# Accelerometer.net
KiCad netlist of a schematic drawn in Altium Designer
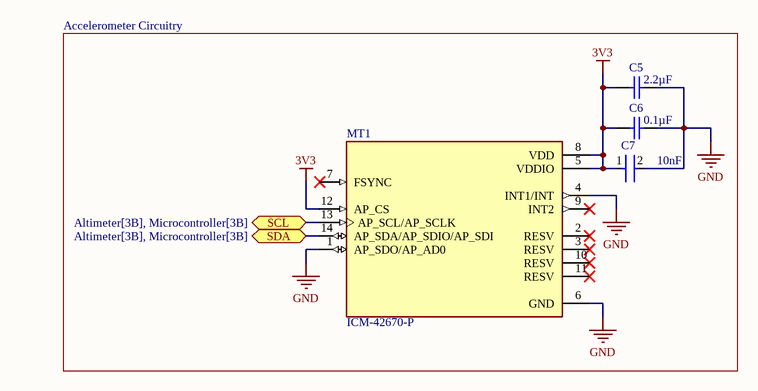
[diagram p0: Accelerometer.SchDoc]

(export (version "E")
  (design (tool "Eeschema 10.0.6"))
  (components
    (comp (ref "C5")
      (value "2.2µF")
      (footprint "CAPC3216X180X50LL20T25")
      (description "Chip Capacitor, 2.2 uF, +/- 10%, 50 V, -55 to 125 degC, 1206 (3216 Metric), RoHS, Tape and Reel")
      (fields (field (name "MANUFACTURER") "Kemet") (field (name "TOLERANCE") "10%"))
      (libsource (lib "Altium Content Vault") (part "CAP-NP-2"))
    )
    (comp (ref "C6")
      (value "0.1µF")
      (footprint "CAPC3216X100X50LL20T25")
      (description "Chip Capacitor, 100 nF, +/- 10%, 25 V, -55 to 125 degC, 1206 (3216 Metric), RoHS, Tape and Reel")
      (fields (field (name "MANUFACTURER") "Kemet"))
      (libsource (lib "") (part "CAP-NP-2_1"))
    )
    (comp (ref "C7")
      (value "10nF")
      (footprint "FP-C1206C-EB-MFG")
      (description "CAP CER 10000PF 100V X7R 1206")
      (fields
        (field (name "OCTOPART") "https://octopart.com/c1206c103j1ractu-kemet-121270")
        (field (name "MANUFACTURER") "KEMET")
      )
      (libsource (lib "Altium Content Vault") (part "b4654b650e69147ec39a6b967a45e02"))
    )
    (comp (ref "MT1")
      (value "ICM-42670-P")
      (footprint "XDCR_ICM-42670-P")
      (libsource (lib "ICM-42670-P") (part "ICM-42670-P"))
    )
  )
  (nets
    (net (code "1") (name "/SCL") (class "Default")
      (node (ref "MT1") (pin "13") (pinfunction "AP_SCL/AP_SCLK_13") (pintype "input"))
    )
    (net (code "2") (name "/SDA") (class "Default")
      (node (ref "MT1") (pin "14") (pinfunction "AP_SDA/AP_SDIO/AP_SDI_14") (pintype "bidirectional"))
    )
    (net (code "3") (name "3V3") (class "Default")
      (node (ref "C5") (pin "2") (pinfunction "2_2") (pintype "passive"))
      (node (ref "C6") (pin "2") (pinfunction "2_2") (pintype "passive"))
      (node (ref "C7") (pin "1") (pinfunction "1_1") (pintype "passive"))
      (node (ref "MT1") (pin "12") (pinfunction "AP_CS_12") (pintype "input"))
      (node (ref "MT1") (pin "5") (pinfunction "VDDIO_5") (pintype "power_in"))
      (node (ref "MT1") (pin "8") (pinfunction "VDD_8") (pintype "power_in"))
    )
    (net (code "4") (name "GND") (class "Default")
      (node (ref "C5") (pin "1") (pinfunction "1_1") (pintype "passive"))
      (node (ref "C6") (pin "1") (pinfunction "1_1") (pintype "passive"))
      (node (ref "C7") (pin "2") (pinfunction "2_2") (pintype "passive"))
      (node (ref "MT1") (pin "1") (pinfunction "AP_SDO/AP_AD0_1") (pintype "bidirectional"))
      (node (ref "MT1") (pin "4") (pinfunction "INT1/INT_4") (pintype "output"))
      (node (ref "MT1") (pin "6") (pinfunction "GND_6") (pintype "power_in"))
    )
    (net (code "5") (name "unconnected-(MT1-FSYNC-Pad7)") (class "Default")
      (node (ref "MT1") (pin "7") (pinfunction "FSYNC_7") (pintype "input+no_connect"))
    )
    (net (code "6") (name "unconnected-(MT1-INT2-Pad9)") (class "Default")
      (node (ref "MT1") (pin "9") (pinfunction "INT2_9") (pintype "output+no_connect"))
    )
    (net (code "7") (name "unconnected-(MT1-RESV-Pad2)") (class "Default")
      (node (ref "MT1") (pin "2") (pinfunction "RESV_2") (pintype "passive+no_connect"))
    )
    (net (code "8") (name "unconnected-(MT1-RESV-Pad3)") (class "Default")
      (node (ref "MT1") (pin "3") (pinfunction "RESV_3") (pintype "passive+no_connect"))
    )
    (net (code "9") (name "unconnected-(MT1-RESV-Pad10)") (class "Default")
      (node (ref "MT1") (pin "10") (pinfunction "RESV_10") (pintype "passive+no_connect"))
    )
    (net (code "10") (name "unconnected-(MT1-RESV-Pad11)") (class "Default")
      (node (ref "MT1") (pin "11") (pinfunction "RESV_11") (pintype "passive+no_connect"))
    )
  )
)
